# Board_v1.net
KiCad netlist of a schematic drawn in EAGLE
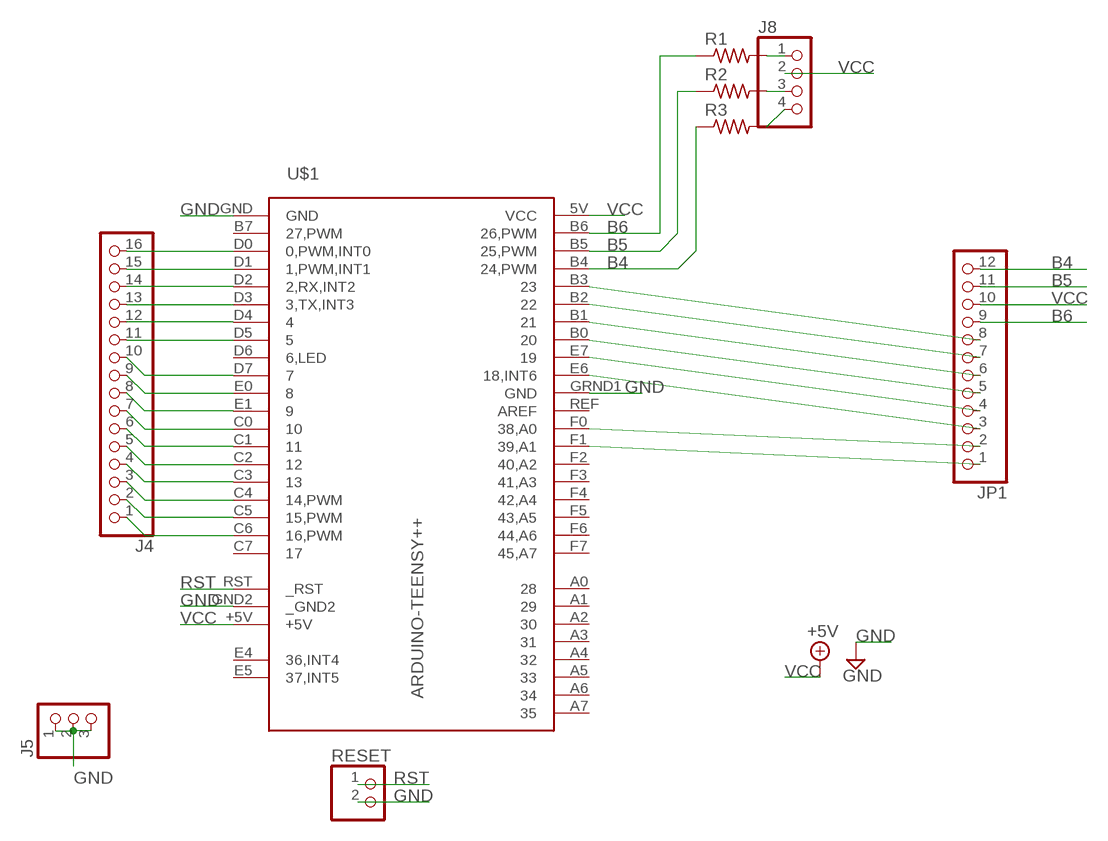
[diagram p0: schematic, sheet 1]

(export (version "E")
  (design (tool "Eeschema 10.0.6"))
  (components
    (comp (ref "J4")
      (value "PINHD-1X16")
      (footprint "eagle-import:1X16")
      (libsource (lib "eagle-import") (part "PINHD-1X16"))
    )
    (comp (ref "J5")
      (value "PINHD-1X3")
      (footprint "eagle-import:1X03")
      (libsource (lib "eagle-import") (part "PINHD-1X3"))
    )
    (comp (ref "J8")
      (value "PINHD-1X4")
      (footprint "eagle-import:1X04")
      (libsource (lib "eagle-import") (part "PINHD-1X4"))
    )
    (comp (ref "JP1")
      (value "PINHD-1X12")
      (footprint "eagle-import:1X12")
      (libsource (lib "eagle-import") (part "PINHD-1X12"))
    )
    (comp (ref "R1")
      (value "R-US_R0805")
      (footprint "eagle-import:R0805")
      (libsource (lib "eagle-import") (part "R-US_R0805"))
    )
    (comp (ref "R2")
      (value "R-US_R0805")
      (footprint "eagle-import:R0805")
      (libsource (lib "eagle-import") (part "R-US_R0805"))
    )
    (comp (ref "R3")
      (value "R-US_R0805")
      (footprint "eagle-import:R0805")
      (libsource (lib "eagle-import") (part "R-US_R0805"))
    )
    (comp (ref "RESET")
      (value "PINHD-1X2")
      (footprint "eagle-import:1X02")
      (libsource (lib "eagle-import") (part "PINHD-1X2"))
    )
    (comp (ref "U$1")
      (value "ARDUINO-TEENSY++")
      (footprint "eagle-import:TEENSY++")
      (libsource (lib "eagle-import") (part "ARDUINO-TEENSY++"))
    )
  )
  (nets
    (net (code "1") (name "+5V") (class "Default")
      (node (ref "J8") (pin "2") (pinfunction "2_2") (pintype "passive"))
      (node (ref "JP1") (pin "10") (pinfunction "10_10") (pintype "passive"))
      (node (ref "U$1") (pin "+5V") (pinfunction "+5V_+5V") (pintype "power_in"))
      (node (ref "U$1") (pin "5V") (pinfunction "VCC_5V") (pintype "power_in"))
    )
    (net (code "2") (name "/B4") (class "Default")
      (node (ref "JP1") (pin "12") (pinfunction "12_12") (pintype "passive"))
      (node (ref "R3") (pin "1") (pinfunction "1_1") (pintype "passive"))
      (node (ref "U$1") (pin "B4") (pinfunction "24,PWM_B4") (pintype "bidirectional"))
    )
    (net (code "3") (name "/B5") (class "Default")
      (node (ref "JP1") (pin "11") (pinfunction "11_11") (pintype "passive"))
      (node (ref "R2") (pin "1") (pinfunction "1_1") (pintype "passive"))
      (node (ref "U$1") (pin "B5") (pinfunction "25,PWM_B5") (pintype "bidirectional"))
    )
    (net (code "4") (name "/B6") (class "Default")
      (node (ref "JP1") (pin "9") (pinfunction "9_9") (pintype "passive"))
      (node (ref "R1") (pin "1") (pinfunction "1_1") (pintype "passive"))
      (node (ref "U$1") (pin "B6") (pinfunction "26,PWM_B6") (pintype "bidirectional"))
    )
    (net (code "5") (name "/RST") (class "Default")
      (node (ref "RESET") (pin "1") (pinfunction "1_1") (pintype "passive"))
      (node (ref "U$1") (pin "RST") (pinfunction "_RST_RST") (pintype "input"))
    )
    (net (code "6") (name "GND") (class "Default")
      (node (ref "J5") (pin "1") (pinfunction "1_1") (pintype "passive"))
      (node (ref "J5") (pin "2") (pinfunction "2_2") (pintype "passive"))
      (node (ref "J5") (pin "3") (pinfunction "3_3") (pintype "passive"))
      (node (ref "RESET") (pin "2") (pinfunction "2_2") (pintype "passive"))
      (node (ref "U$1") (pin "GND") (pinfunction "GND_GND") (pintype "power_in"))
      (node (ref "U$1") (pin "GND2") (pinfunction "_GND2_GND2") (pintype "power_in"))
      (node (ref "U$1") (pin "GRND1") (pinfunction "GND_GRND1") (pintype "power_in"))
    )
    (net (code "7") (name "Net-(J8-Pad1)") (class "Default")
      (node (ref "J8") (pin "1") (pinfunction "1_1") (pintype "passive"))
      (node (ref "R1") (pin "2") (pinfunction "2_2") (pintype "passive"))
    )
    (net (code "8") (name "Net-(J8-Pad3)") (class "Default")
      (node (ref "J8") (pin "3") (pinfunction "3_3") (pintype "passive"))
      (node (ref "R2") (pin "2") (pinfunction "2_2") (pintype "passive"))
    )
    (net (code "9") (name "Net-(J8-Pad4)") (class "Default")
      (node (ref "J8") (pin "4") (pinfunction "4_4") (pintype "passive"))
      (node (ref "R3") (pin "2") (pinfunction "2_2") (pintype "passive"))
    )
    (net (code "10") (name "Net-(U$1-0,PWM,INT0)") (class "Default")
      (node (ref "J4") (pin "16") (pinfunction "16_16") (pintype "passive"))
      (node (ref "U$1") (pin "D0") (pinfunction "0,PWM,INT0_D0") (pintype "bidirectional"))
    )
    (net (code "11") (name "Net-(U$1-1,PWM,INT1)") (class "Default")
      (node (ref "J4") (pin "15") (pinfunction "15_15") (pintype "passive"))
      (node (ref "U$1") (pin "D1") (pinfunction "1,PWM,INT1_D1") (pintype "bidirectional"))
    )
    (net (code "12") (name "Net-(U$1-2,RX,INT2)") (class "Default")
      (node (ref "J4") (pin "14") (pinfunction "14_14") (pintype "passive"))
      (node (ref "U$1") (pin "D2") (pinfunction "2,RX,INT2_D2") (pintype "bidirectional"))
    )
    (net (code "13") (name "Net-(U$1-3,TX,INT3)") (class "Default")
      (node (ref "J4") (pin "13") (pinfunction "13_13") (pintype "passive"))
      (node (ref "U$1") (pin "D3") (pinfunction "3,TX,INT3_D3") (pintype "bidirectional"))
    )
    (net (code "14") (name "Net-(U$1-4)") (class "Default")
      (node (ref "J4") (pin "12") (pinfunction "12_12") (pintype "passive"))
      (node (ref "U$1") (pin "D4") (pinfunction "4_D4") (pintype "bidirectional"))
    )
    (net (code "15") (name "Net-(U$1-5)") (class "Default")
      (node (ref "J4") (pin "11") (pinfunction "11_11") (pintype "passive"))
      (node (ref "U$1") (pin "D5") (pinfunction "5_D5") (pintype "bidirectional"))
    )
    (net (code "16") (name "Net-(U$1-7)") (class "Default")
      (node (ref "J4") (pin "10") (pinfunction "10_10") (pintype "passive"))
      (node (ref "U$1") (pin "D7") (pinfunction "7_D7") (pintype "bidirectional"))
    )
    (net (code "17") (name "Net-(U$1-8)") (class "Default")
      (node (ref "J4") (pin "9") (pinfunction "9_9") (pintype "passive"))
      (node (ref "U$1") (pin "E0") (pinfunction "8_E0") (pintype "bidirectional"))
    )
    (net (code "18") (name "Net-(U$1-9)") (class "Default")
      (node (ref "J4") (pin "8") (pinfunction "8_8") (pintype "passive"))
      (node (ref "U$1") (pin "E1") (pinfunction "9_E1") (pintype "bidirectional"))
    )
    (net (code "19") (name "Net-(U$1-10)") (class "Default")
      (node (ref "J4") (pin "7") (pinfunction "7_7") (pintype "passive"))
      (node (ref "U$1") (pin "C0") (pinfunction "10_C0") (pintype "bidirectional"))
    )
    (net (code "20") (name "Net-(U$1-11)") (class "Default")
      (node (ref "J4") (pin "6") (pinfunction "6_6") (pintype "passive"))
      (node (ref "U$1") (pin "C1") (pinfunction "11_C1") (pintype "bidirectional"))
    )
    (net (code "21") (name "Net-(U$1-12)") (class "Default")
      (node (ref "J4") (pin "5") (pinfunction "5_5") (pintype "passive"))
      (node (ref "U$1") (pin "C2") (pinfunction "12_C2") (pintype "bidirectional"))
    )
    (net (code "22") (name "Net-(U$1-13)") (class "Default")
      (node (ref "J4") (pin "4") (pinfunction "4_4") (pintype "passive"))
      (node (ref "U$1") (pin "C3") (pinfunction "13_C3") (pintype "bidirectional"))
    )
    (net (code "23") (name "Net-(U$1-14,PWM)") (class "Default")
      (node (ref "J4") (pin "3") (pinfunction "3_3") (pintype "passive"))
      (node (ref "U$1") (pin "C4") (pinfunction "14,PWM_C4") (pintype "bidirectional"))
    )
    (net (code "24") (name "Net-(U$1-15,PWM)") (class "Default")
      (node (ref "J4") (pin "2") (pinfunction "2_2") (pintype "passive"))
      (node (ref "U$1") (pin "C5") (pinfunction "15,PWM_C5") (pintype "bidirectional"))
    )
    (net (code "25") (name "Net-(U$1-16,PWM)") (class "Default")
      (node (ref "J4") (pin "1") (pinfunction "1_1") (pintype "passive"))
      (node (ref "U$1") (pin "C6") (pinfunction "16,PWM_C6") (pintype "bidirectional"))
    )
    (net (code "26") (name "Net-(U$1-18,INT6)") (class "Default")
      (node (ref "JP1") (pin "3") (pinfunction "3_3") (pintype "passive"))
      (node (ref "U$1") (pin "E6") (pinfunction "18,INT6_E6") (pintype "bidirectional"))
    )
    (net (code "27") (name "Net-(U$1-19)") (class "Default")
      (node (ref "JP1") (pin "4") (pinfunction "4_4") (pintype "passive"))
      (node (ref "U$1") (pin "E7") (pinfunction "19_E7") (pintype "bidirectional"))
    )
    (net (code "28") (name "Net-(U$1-20)") (class "Default")
      (node (ref "JP1") (pin "5") (pinfunction "5_5") (pintype "passive"))
      (node (ref "U$1") (pin "B0") (pinfunction "20_B0") (pintype "bidirectional"))
    )
    (net (code "29") (name "Net-(U$1-21)") (class "Default")
      (node (ref "JP1") (pin "6") (pinfunction "6_6") (pintype "passive"))
      (node (ref "U$1") (pin "B1") (pinfunction "21_B1") (pintype "bidirectional"))
    )
    (net (code "30") (name "Net-(U$1-22)") (class "Default")
      (node (ref "JP1") (pin "7") (pinfunction "7_7") (pintype "passive"))
      (node (ref "U$1") (pin "B2") (pinfunction "22_B2") (pintype "bidirectional"))
    )
    (net (code "31") (name "Net-(U$1-23)") (class "Default")
      (node (ref "JP1") (pin "8") (pinfunction "8_8") (pintype "passive"))
      (node (ref "U$1") (pin "B3") (pinfunction "23_B3") (pintype "bidirectional"))
    )
    (net (code "32") (name "Net-(U$1-38,A0)") (class "Default")
      (node (ref "JP1") (pin "2") (pinfunction "2_2") (pintype "passive"))
      (node (ref "U$1") (pin "F0") (pinfunction "38,A0_F0") (pintype "bidirectional"))
    )
    (net (code "33") (name "Net-(U$1-39,A1)") (class "Default")
      (node (ref "JP1") (pin "1") (pinfunction "1_1") (pintype "passive"))
      (node (ref "U$1") (pin "F1") (pinfunction "39,A1_F1") (pintype "bidirectional"))
    )
    (net (code "34") (name "unconnected-(U$1-6,LED-PadD6)") (class "Default")
      (node (ref "U$1") (pin "D6") (pinfunction "6,LED_D6") (pintype "bidirectional"))
    )
    (net (code "35") (name "unconnected-(U$1-17-PadC7)") (class "Default")
      (node (ref "U$1") (pin "C7") (pinfunction "17_C7") (pintype "bidirectional"))
    )
    (net (code "36") (name "unconnected-(U$1-27,PWM-PadB7)") (class "Default")
      (node (ref "U$1") (pin "B7") (pinfunction "27,PWM_B7") (pintype "bidirectional"))
    )
    (net (code "37") (name "unconnected-(U$1-28-PadA0)") (class "Default")
      (node (ref "U$1") (pin "A0") (pinfunction "28_A0") (pintype "bidirectional"))
    )
    (net (code "38") (name "unconnected-(U$1-29-PadA1)") (class "Default")
      (node (ref "U$1") (pin "A1") (pinfunction "29_A1") (pintype "bidirectional"))
    )
    (net (code "39") (name "unconnected-(U$1-30-PadA2)") (class "Default")
      (node (ref "U$1") (pin "A2") (pinfunction "30_A2") (pintype "bidirectional"))
    )
    (net (code "40") (name "unconnected-(U$1-31-PadA3)") (class "Default")
      (node (ref "U$1") (pin "A3") (pinfunction "31_A3") (pintype "bidirectional"))
    )
    (net (code "41") (name "unconnected-(U$1-32-PadA4)") (class "Default")
      (node (ref "U$1") (pin "A4") (pinfunction "32_A4") (pintype "bidirectional"))
    )
    (net (code "42") (name "unconnected-(U$1-33-PadA5)") (class "Default")
      (node (ref "U$1") (pin "A5") (pinfunction "33_A5") (pintype "bidirectional"))
    )
    (net (code "43") (name "unconnected-(U$1-34-PadA6)") (class "Default")
      (node (ref "U$1") (pin "A6") (pinfunction "34_A6") (pintype "bidirectional"))
    )
    (net (code "44") (name "unconnected-(U$1-35-PadA7)") (class "Default")
      (node (ref "U$1") (pin "A7") (pinfunction "35_A7") (pintype "bidirectional"))
    )
    (net (code "45") (name "unconnected-(U$1-36,INT4-PadE4)") (class "Default")
      (node (ref "U$1") (pin "E4") (pinfunction "36,INT4_E4") (pintype "bidirectional"))
    )
    (net (code "46") (name "unconnected-(U$1-37,INT5-PadE5)") (class "Default")
      (node (ref "U$1") (pin "E5") (pinfunction "37,INT5_E5") (pintype "bidirectional"))
    )
    (net (code "47") (name "unconnected-(U$1-40,A2-PadF2)") (class "Default")
      (node (ref "U$1") (pin "F2") (pinfunction "40,A2_F2") (pintype "bidirectional"))
    )
    (net (code "48") (name "unconnected-(U$1-41,A3-PadF3)") (class "Default")
      (node (ref "U$1") (pin "F3") (pinfunction "41,A3_F3") (pintype "bidirectional"))
    )
    (net (code "49") (name "unconnected-(U$1-42,A4-PadF4)") (class "Default")
      (node (ref "U$1") (pin "F4") (pinfunction "42,A4_F4") (pintype "bidirectional"))
    )
    (net (code "50") (name "unconnected-(U$1-43,A5-PadF5)") (class "Default")
      (node (ref "U$1") (pin "F5") (pinfunction "43,A5_F5") (pintype "bidirectional"))
    )
    (net (code "51") (name "unconnected-(U$1-44,A6-PadF6)") (class "Default")
      (node (ref "U$1") (pin "F6") (pinfunction "44,A6_F6") (pintype "bidirectional"))
    )
    (net (code "52") (name "unconnected-(U$1-45,A7-PadF7)") (class "Default")
      (node (ref "U$1") (pin "F7") (pinfunction "45,A7_F7") (pintype "bidirectional"))
    )
    (net (code "53") (name "unconnected-(U$1-AREF-PadREF)") (class "Default")
      (node (ref "U$1") (pin "REF") (pinfunction "AREF_REF") (pintype "input"))
    )
  )
)
